# Control.net
KiCad netlist of a schematic drawn in EAGLE
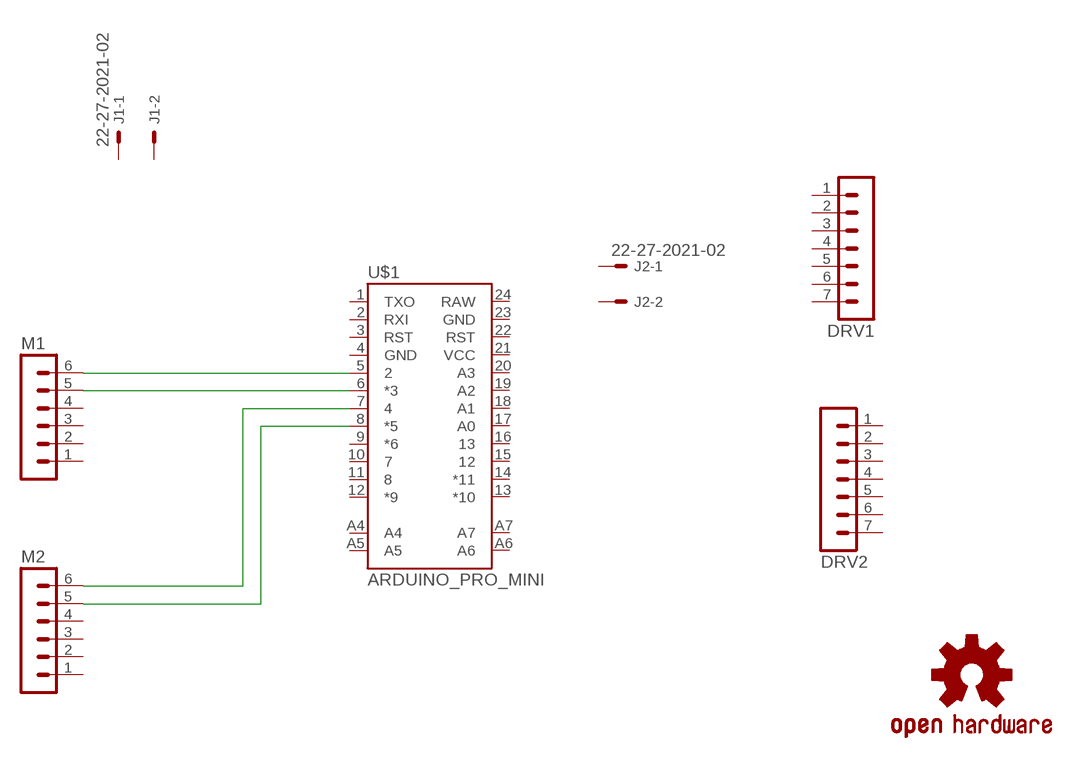
[diagram p0: schematic, sheet 1]

(export (version "E")
  (design (tool "Eeschema 10.0.6"))
  (components
    (comp (ref "DRV1")
      (value "MA07-1")
      (footprint "eagle-import:MA07-1")
      (libsource (lib "eagle-import") (part "MA07-1"))
    )
    (comp (ref "DRV2")
      (value "MA07-1")
      (footprint "eagle-import:MA07-1")
      (libsource (lib "eagle-import") (part "MA07-1"))
    )
    (comp (ref "J1")
      (value "22-27-2021-02")
      (footprint "eagle-import:6410-02")
      (libsource (lib "eagle-import") (part "22-?-0227-2021"))
    )
    (comp (ref "J2")
      (value "22-27-2021-02")
      (footprint "eagle-import:6410-02")
      (libsource (lib "eagle-import") (part "22-?-0227-2021"))
    )
    (comp (ref "LOGO1")
      (value "OSHW-LOGOL-COPPER")
      (footprint "eagle-import:OSHW-LOGO-L_COPPER")
      (libsource (lib "eagle-import") (part "OSHW-LOGOL-COPPER"))
    )
    (comp (ref "M1")
      (value "MA06-1")
      (footprint "eagle-import:MA06-1")
      (libsource (lib "eagle-import") (part "MA06-1"))
    )
    (comp (ref "M2")
      (value "MA06-1")
      (footprint "eagle-import:MA06-1")
      (libsource (lib "eagle-import") (part "MA06-1"))
    )
    (comp (ref "U$1")
      (value "ARDUINO_PRO_MINI")
      (footprint "eagle-import:ARDUINO_PRO_MINI")
      (libsource (lib "eagle-import") (part "ARDUINO_PRO_MINI"))
    )
  )
  (nets
    (net (code "1") (name "Net-(U$1-*3)") (class "Default")
      (node (ref "M1") (pin "5") (pinfunction "5_5") (pintype "passive"))
      (node (ref "U$1") (pin "6") (pinfunction "*3_6") (pintype "bidirectional"))
    )
    (net (code "2") (name "Net-(U$1-*5)") (class "Default")
      (node (ref "M2") (pin "5") (pinfunction "5_5") (pintype "passive"))
      (node (ref "U$1") (pin "8") (pinfunction "*5_8") (pintype "bidirectional"))
    )
    (net (code "3") (name "Net-(U$1-2)") (class "Default")
      (node (ref "M1") (pin "6") (pinfunction "6_6") (pintype "passive"))
      (node (ref "U$1") (pin "5") (pinfunction "2_5") (pintype "bidirectional"))
    )
    (net (code "4") (name "Net-(U$1-4)") (class "Default")
      (node (ref "M2") (pin "6") (pinfunction "6_6") (pintype "passive"))
      (node (ref "U$1") (pin "7") (pinfunction "4_7") (pintype "bidirectional"))
    )
    (net (code "5") (name "unconnected-(DRV1-Pad1)") (class "Default")
      (node (ref "DRV1") (pin "1") (pinfunction "1_1") (pintype "passive"))
    )
    (net (code "6") (name "unconnected-(DRV1-Pad2)") (class "Default")
      (node (ref "DRV1") (pin "2") (pinfunction "2_2") (pintype "passive"))
    )
    (net (code "7") (name "unconnected-(DRV1-Pad3)") (class "Default")
      (node (ref "DRV1") (pin "3") (pinfunction "3_3") (pintype "passive"))
    )
    (net (code "8") (name "unconnected-(DRV1-Pad4)") (class "Default")
      (node (ref "DRV1") (pin "4") (pinfunction "4_4") (pintype "passive"))
    )
    (net (code "9") (name "unconnected-(DRV1-Pad5)") (class "Default")
      (node (ref "DRV1") (pin "5") (pinfunction "5_5") (pintype "passive"))
    )
    (net (code "10") (name "unconnected-(DRV1-Pad6)") (class "Default")
      (node (ref "DRV1") (pin "6") (pinfunction "6_6") (pintype "passive"))
    )
    (net (code "11") (name "unconnected-(DRV1-Pad7)") (class "Default")
      (node (ref "DRV1") (pin "7") (pinfunction "7_7") (pintype "passive"))
    )
    (net (code "12") (name "unconnected-(DRV2-Pad1)") (class "Default")
      (node (ref "DRV2") (pin "1") (pinfunction "1_1") (pintype "passive"))
    )
    (net (code "13") (name "unconnected-(DRV2-Pad2)") (class "Default")
      (node (ref "DRV2") (pin "2") (pinfunction "2_2") (pintype "passive"))
    )
    (net (code "14") (name "unconnected-(DRV2-Pad3)") (class "Default")
      (node (ref "DRV2") (pin "3") (pinfunction "3_3") (pintype "passive"))
    )
    (net (code "15") (name "unconnected-(DRV2-Pad4)") (class "Default")
      (node (ref "DRV2") (pin "4") (pinfunction "4_4") (pintype "passive"))
    )
    (net (code "16") (name "unconnected-(DRV2-Pad5)") (class "Default")
      (node (ref "DRV2") (pin "5") (pinfunction "5_5") (pintype "passive"))
    )
    (net (code "17") (name "unconnected-(DRV2-Pad6)") (class "Default")
      (node (ref "DRV2") (pin "6") (pinfunction "6_6") (pintype "passive"))
    )
    (net (code "18") (name "unconnected-(DRV2-Pad7)") (class "Default")
      (node (ref "DRV2") (pin "7") (pinfunction "7_7") (pintype "passive"))
    )
    (net (code "19") (name "unconnected-(J1A-S-Pad1)") (class "Default")
      (node (ref "J1") (pin "1") (pinfunction "S_1") (pintype "passive"))
    )
    (net (code "20") (name "unconnected-(J1B-S-Pad2)") (class "Default")
      (node (ref "J1") (pin "2") (pinfunction "S_2") (pintype "passive"))
    )
    (net (code "21") (name "unconnected-(J2A-S-Pad1)") (class "Default")
      (node (ref "J2") (pin "1") (pinfunction "S_1") (pintype "passive"))
    )
    (net (code "22") (name "unconnected-(J2B-S-Pad2)") (class "Default")
      (node (ref "J2") (pin "2") (pinfunction "S_2") (pintype "passive"))
    )
    (net (code "23") (name "unconnected-(M1-Pad1)") (class "Default")
      (node (ref "M1") (pin "1") (pinfunction "1_1") (pintype "passive"))
    )
    (net (code "24") (name "unconnected-(M1-Pad2)") (class "Default")
      (node (ref "M1") (pin "2") (pinfunction "2_2") (pintype "passive"))
    )
    (net (code "25") (name "unconnected-(M1-Pad3)") (class "Default")
      (node (ref "M1") (pin "3") (pinfunction "3_3") (pintype "passive"))
    )
    (net (code "26") (name "unconnected-(M1-Pad4)") (class "Default")
      (node (ref "M1") (pin "4") (pinfunction "4_4") (pintype "passive"))
    )
    (net (code "27") (name "unconnected-(M2-Pad1)") (class "Default")
      (node (ref "M2") (pin "1") (pinfunction "1_1") (pintype "passive"))
    )
    (net (code "28") (name "unconnected-(M2-Pad2)") (class "Default")
      (node (ref "M2") (pin "2") (pinfunction "2_2") (pintype "passive"))
    )
    (net (code "29") (name "unconnected-(M2-Pad3)") (class "Default")
      (node (ref "M2") (pin "3") (pinfunction "3_3") (pintype "passive"))
    )
    (net (code "30") (name "unconnected-(M2-Pad4)") (class "Default")
      (node (ref "M2") (pin "4") (pinfunction "4_4") (pintype "passive"))
    )
    (net (code "31") (name "unconnected-(U$1-*6-Pad9)") (class "Default")
      (node (ref "U$1") (pin "9") (pinfunction "*6_9") (pintype "bidirectional"))
    )
    (net (code "32") (name "unconnected-(U$1-*9-Pad12)") (class "Default")
      (node (ref "U$1") (pin "12") (pinfunction "*9_12") (pintype "bidirectional"))
    )
    (net (code "33") (name "unconnected-(U$1-*10-Pad13)") (class "Default")
      (node (ref "U$1") (pin "13") (pinfunction "*10_13") (pintype "bidirectional"))
    )
    (net (code "34") (name "unconnected-(U$1-*11-Pad14)") (class "Default")
      (node (ref "U$1") (pin "14") (pinfunction "*11_14") (pintype "bidirectional"))
    )
    (net (code "35") (name "unconnected-(U$1-7-Pad10)") (class "Default")
      (node (ref "U$1") (pin "10") (pinfunction "7_10") (pintype "bidirectional"))
    )
    (net (code "36") (name "unconnected-(U$1-8-Pad11)") (class "Default")
      (node (ref "U$1") (pin "11") (pinfunction "8_11") (pintype "bidirectional"))
    )
    (net (code "37") (name "unconnected-(U$1-12-Pad15)") (class "Default")
      (node (ref "U$1") (pin "15") (pinfunction "12_15") (pintype "bidirectional"))
    )
    (net (code "38") (name "unconnected-(U$1-13-Pad16)") (class "Default")
      (node (ref "U$1") (pin "16") (pinfunction "13_16") (pintype "bidirectional"))
    )
    (net (code "39") (name "unconnected-(U$1-A0-Pad17)") (class "Default")
      (node (ref "U$1") (pin "17") (pinfunction "A0_17") (pintype "bidirectional"))
    )
    (net (code "40") (name "unconnected-(U$1-A1-Pad18)") (class "Default")
      (node (ref "U$1") (pin "18") (pinfunction "A1_18") (pintype "bidirectional"))
    )
    (net (code "41") (name "unconnected-(U$1-A2-Pad19)") (class "Default")
      (node (ref "U$1") (pin "19") (pinfunction "A2_19") (pintype "bidirectional"))
    )
    (net (code "42") (name "unconnected-(U$1-A3-Pad20)") (class "Default")
      (node (ref "U$1") (pin "20") (pinfunction "A3_20") (pintype "bidirectional"))
    )
    (net (code "43") (name "unconnected-(U$1-GND-Pad4)") (class "Default")
      (node (ref "U$1") (pin "4") (pinfunction "GND_4") (pintype "bidirectional"))
    )
    (net (code "44") (name "unconnected-(U$1-GND-Pad23)") (class "Default")
      (node (ref "U$1") (pin "23") (pinfunction "GND_23") (pintype "bidirectional"))
    )
    (net (code "45") (name "unconnected-(U$1-PadA4)") (class "Default")
      (node (ref "U$1") (pin "A4") (pinfunction "A4_A4") (pintype "bidirectional"))
    )
    (net (code "46") (name "unconnected-(U$1-PadA5)") (class "Default")
      (node (ref "U$1") (pin "A5") (pinfunction "A5_A5") (pintype "bidirectional"))
    )
    (net (code "47") (name "unconnected-(U$1-PadA6)") (class "Default")
      (node (ref "U$1") (pin "A6") (pinfunction "A6_A6") (pintype "bidirectional"))
    )
    (net (code "48") (name "unconnected-(U$1-PadA7)") (class "Default")
      (node (ref "U$1") (pin "A7") (pinfunction "A7_A7") (pintype "bidirectional"))
    )
    (net (code "49") (name "unconnected-(U$1-RAW-Pad24)") (class "Default")
      (node (ref "U$1") (pin "24") (pinfunction "RAW_24") (pintype "bidirectional"))
    )
    (net (code "50") (name "unconnected-(U$1-RST-Pad3)") (class "Default")
      (node (ref "U$1") (pin "3") (pinfunction "RST_3") (pintype "bidirectional"))
    )
    (net (code "51") (name "unconnected-(U$1-RST-Pad22)") (class "Default")
      (node (ref "U$1") (pin "22") (pinfunction "RST_22") (pintype "bidirectional"))
    )
    (net (code "52") (name "unconnected-(U$1-RXI-Pad2)") (class "Default")
      (node (ref "U$1") (pin "2") (pinfunction "RXI_2") (pintype "bidirectional"))
    )
    (net (code "53") (name "unconnected-(U$1-TXO-Pad1)") (class "Default")
      (node (ref "U$1") (pin "1") (pinfunction "TXO_1") (pintype "bidirectional"))
    )
    (net (code "54") (name "unconnected-(U$1-VCC-Pad21)") (class "Default")
      (node (ref "U$1") (pin "21") (pinfunction "VCC_21") (pintype "bidirectional"))
    )
  )
)
